# 1_J_LINK_PCB.net
KiCad netlist of a schematic drawn in EasyEDA Pro
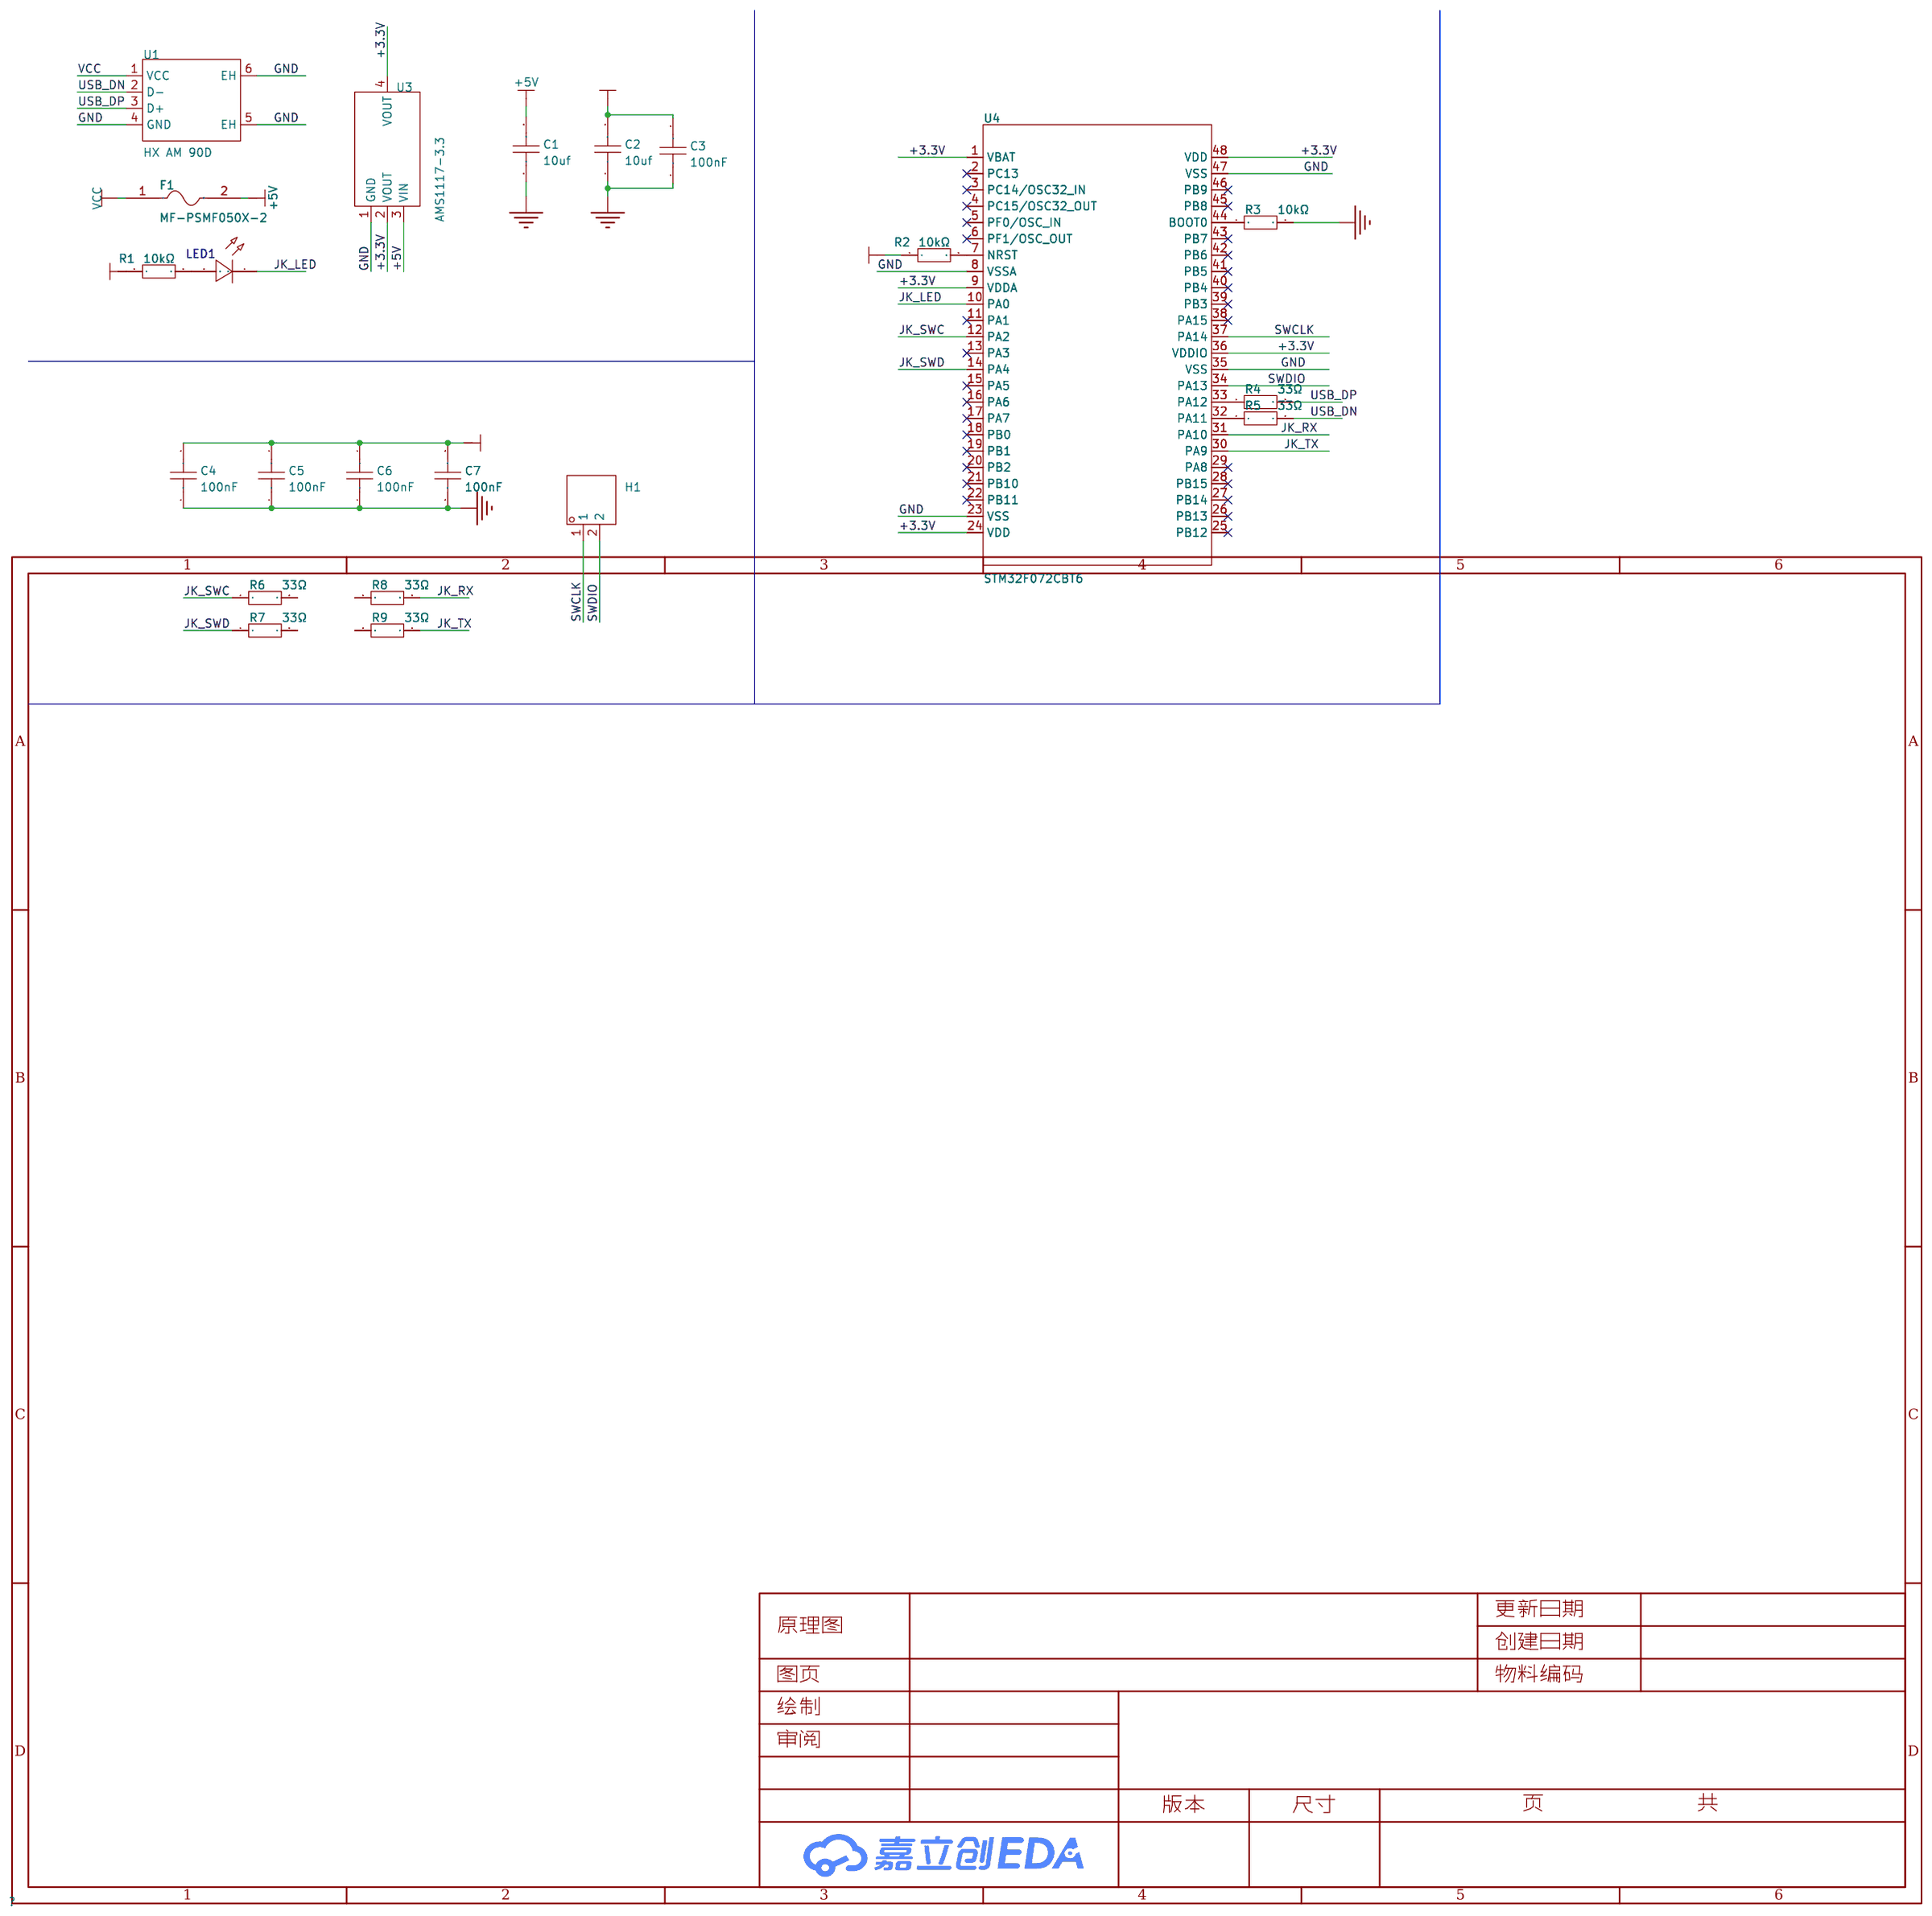
[diagram p0: schematic sheet]

(export (version "E")
  (design (tool "Eeschema 10.0.6"))
  (components
    (comp (ref "C1")
      (value "10uf")
      (footprint "easyedapro:C0603")
      (libsource (lib "easyedapro") (part "CapAcitance"))
    )
    (comp (ref "C2")
      (value "10uf")
      (footprint "easyedapro:C0603")
      (libsource (lib "easyedapro") (part "CapAcitance"))
    )
    (comp (ref "C3")
      (value "100nF")
      (footprint "easyedapro:C0603")
      (libsource (lib "easyedapro") (part "CapAcitance"))
    )
    (comp (ref "C4")
      (value "100nF")
      (footprint "easyedapro:C0603")
      (description "容值:100nF;精度:±10%;额定电压:50V;温度系数:X7R;")
      (fields
        (field (name "Manufacturer Part") "CGA0603X7R104K500JT")
        (field (name "Manufacturer") "HRE(芯声)")
      )
      (libsource (lib "easyedapro") (part "CGA0603X7R104K500JT"))
    )
    (comp (ref "C5")
      (value "100nF")
      (footprint "easyedapro:C0603")
      (description "容值:100nF;精度:±10%;额定电压:50V;温度系数:X7R;")
      (fields
        (field (name "Manufacturer Part") "CGA0603X7R104K500JT")
        (field (name "Manufacturer") "HRE(芯声)")
      )
      (libsource (lib "easyedapro") (part "CGA0603X7R104K500JT"))
    )
    (comp (ref "C6")
      (value "100nF")
      (footprint "easyedapro:C0603")
      (description "容值:100nF;精度:±10%;额定电压:50V;温度系数:X7R;")
      (fields
        (field (name "Manufacturer Part") "CGA0603X7R104K500JT")
        (field (name "Manufacturer") "HRE(芯声)")
      )
      (libsource (lib "easyedapro") (part "CGA0603X7R104K500JT"))
    )
    (comp (ref "C7")
      (value "100nF")
      (footprint "easyedapro:C0603")
      (description "容值:100nF;精度:±10%;额定电压:50V;温度系数:X7R;")
      (fields
        (field (name "Manufacturer Part") "CGA0603X7R104K500JT")
        (field (name "Manufacturer") "HRE(芯声)")
      )
      (libsource (lib "easyedapro") (part "CGA0603X7R104K500JT"))
    )
    (comp (ref "F1")
      (value "MF-PSMF050X-2")
      (footprint "easyedapro:F0805")
      (description "最大电压:6V;最大电流:40A;保持电流:500mA;跳闸电流:1A;")
      (fields (field (name "Manufacturer") "BOURNS"))
      (libsource (lib "easyedapro") (part "MF-PSMF050X-2"))
    )
    (comp (ref "H1")
      (value "~")
      (footprint "easyedapro:HDR-TH_2P-P2.54-V-M-1")
      (libsource (lib "easyedapro") (part "210S-1*2P L=11.6MMGold-plated black"))
    )
    (comp (ref "LED1")
      (value "~")
      (footprint "easyedapro:LED_0603")
      (libsource (lib "easyedapro") (part "LED_B"))
    )
    (comp (ref "R1")
      (value "10kΩ")
      (footprint "easyedapro:R0603")
      (description "电阻类型:厚膜电阻;阻值:10kΩ;精度:±1%;功率:100mW;最大工作电压:75V;温度系数:±100ppm/°C;")
      (fields
        (field (name "Manufacturer Part") "0603WAF1002T5E")
        (field (name "Manufacturer") "UNI-ROYAL(厚声)")
      )
      (libsource (lib "easyedapro") (part "0603WAF1002T5E"))
    )
    (comp (ref "R2")
      (value "10kΩ")
      (footprint "easyedapro:R0603")
      (description "电阻类型:厚膜电阻;阻值:10kΩ;精度:±1%;功率:100mW;最大工作电压:75V;温度系数:±100ppm/°C;")
      (fields
        (field (name "Manufacturer Part") "0603WAF1002T5E")
        (field (name "Manufacturer") "UNI-ROYAL(厚声)")
      )
      (libsource (lib "easyedapro") (part "0603WAF1002T5E"))
    )
    (comp (ref "R3")
      (value "10kΩ")
      (footprint "easyedapro:R0603")
      (description "电阻类型:厚膜电阻;阻值:10kΩ;精度:±1%;功率:100mW;最大工作电压:75V;温度系数:±100ppm/°C;")
      (fields
        (field (name "Manufacturer Part") "0603WAF1002T5E")
        (field (name "Manufacturer") "UNI-ROYAL(厚声)")
      )
      (libsource (lib "easyedapro") (part "0603WAF1002T5E"))
    )
    (comp (ref "R4")
      (value "33Ω")
      (footprint "easyedapro:R0603")
      (description "电阻类型:厚膜电阻;阻值:10kΩ;精度:±1%;功率:100mW;最大工作电压:75V;温度系数:±100ppm/°C;")
      (fields
        (field (name "Manufacturer Part") "0603WAF1002T5E")
        (field (name "Manufacturer") "UNI-ROYAL(厚声)")
      )
      (libsource (lib "easyedapro") (part "0603WAF1002T5E"))
    )
    (comp (ref "R5")
      (value "33Ω")
      (footprint "easyedapro:R0603")
      (description "电阻类型:厚膜电阻;阻值:10kΩ;精度:±1%;功率:100mW;最大工作电压:75V;温度系数:±100ppm/°C;")
      (fields
        (field (name "Manufacturer Part") "0603WAF1002T5E")
        (field (name "Manufacturer") "UNI-ROYAL(厚声)")
      )
      (libsource (lib "easyedapro") (part "0603WAF1002T5E"))
    )
    (comp (ref "R6")
      (value "33Ω")
      (footprint "easyedapro:R0603")
      (description "电阻类型:厚膜电阻;阻值:10kΩ;精度:±1%;功率:100mW;最大工作电压:75V;温度系数:±100ppm/°C;")
      (fields
        (field (name "Manufacturer Part") "0603WAF1002T5E")
        (field (name "Manufacturer") "UNI-ROYAL(厚声)")
      )
      (libsource (lib "easyedapro") (part "0603WAF1002T5E"))
    )
    (comp (ref "R7")
      (value "33Ω")
      (footprint "easyedapro:R0603")
      (description "电阻类型:厚膜电阻;阻值:10kΩ;精度:±1%;功率:100mW;最大工作电压:75V;温度系数:±100ppm/°C;")
      (fields
        (field (name "Manufacturer Part") "0603WAF1002T5E")
        (field (name "Manufacturer") "UNI-ROYAL(厚声)")
      )
      (libsource (lib "easyedapro") (part "0603WAF1002T5E"))
    )
    (comp (ref "R8")
      (value "33Ω")
      (footprint "easyedapro:R0603")
      (description "电阻类型:厚膜电阻;阻值:10kΩ;精度:±1%;功率:100mW;最大工作电压:75V;温度系数:±100ppm/°C;")
      (fields
        (field (name "Manufacturer Part") "0603WAF1002T5E")
        (field (name "Manufacturer") "UNI-ROYAL(厚声)")
      )
      (libsource (lib "easyedapro") (part "0603WAF1002T5E"))
    )
    (comp (ref "R9")
      (value "33Ω")
      (footprint "easyedapro:R0603")
      (description "电阻类型:厚膜电阻;阻值:10kΩ;精度:±1%;功率:100mW;最大工作电压:75V;温度系数:±100ppm/°C;")
      (fields
        (field (name "Manufacturer Part") "0603WAF1002T5E")
        (field (name "Manufacturer") "UNI-ROYAL(厚声)")
      )
      (libsource (lib "easyedapro") (part "0603WAF1002T5E"))
    )
    (comp (ref "U1")
      (value "HX AM 90D")
      (footprint "easyedapro:USB-A-TH_HANXIA_HXAM90D")
      (description "连接器类型:Type-A;标准:USB 2.0;公母:公;端口数量:1;触点数量:4P;额定电流 - 电源:1.5A;工作温度范围:-25°C~+85°C;")
      (fields (field (name "Manufacturer") "hanxia(韩下)"))
      (libsource (lib "easyedapro") (part "HX AM 90D"))
    )
    (comp (ref "U3")
      (value "AMS1117-3.3")
      (footprint "easyedapro:SOT-223-3_L6.5-W3.4-P2.30-LS7.0-BR")
      (description "输出类型:固定;工作电压:-;输出电压:3.3V;输出电流:1A;电源纹波抑制比(PSRR):72dB@(120Hz);输出极性:正极;")
      (fields (field (name "Manufacturer") "AMS"))
      (libsource (lib "easyedapro") (part "AMS1117-3.3"))
    )
    (comp (ref "U4")
      (value "STM32F072CBT6")
      (footprint "easyedapro:LQFP-48_L7.0-W7.0-P0.50-LS9.0-BL")
      (description "CPU内核:ARM-M0;CPU最大主频:48MHz;应用领域:-;")
      (fields (field (name "Manufacturer") "ST(意法半导体)"))
      (libsource (lib "easyedapro") (part "STM32F072CBT6"))
    )
  )
  (nets
    (net (code "1") (name "+3.3V") (class "Default")
      (node (ref "C2") (pin "2") (pinfunction "2_2") (pintype "input"))
      (node (ref "C3") (pin "2") (pinfunction "2_2") (pintype "input"))
      (node (ref "C4") (pin "2") (pinfunction "2_2") (pintype "unspecified"))
      (node (ref "C5") (pin "2") (pinfunction "2_2") (pintype "unspecified"))
      (node (ref "C6") (pin "2") (pinfunction "2_2") (pintype "unspecified"))
      (node (ref "C7") (pin "2") (pinfunction "2_2") (pintype "unspecified"))
      (node (ref "R1") (pin "1") (pinfunction "1_1") (pintype "input"))
      (node (ref "R2") (pin "1") (pinfunction "1_1") (pintype "input"))
      (node (ref "U3") (pin "2") (pinfunction "VOUT_2") (pintype "unspecified"))
      (node (ref "U3") (pin "4") (pinfunction "VOUT_4") (pintype "unspecified"))
      (node (ref "U4") (pin "1") (pinfunction "VBAT_1") (pintype "unspecified"))
      (node (ref "U4") (pin "24") (pinfunction "VDD_24") (pintype "unspecified"))
      (node (ref "U4") (pin "36") (pinfunction "VDDIO_36") (pintype "unspecified"))
      (node (ref "U4") (pin "48") (pinfunction "VDD_48") (pintype "unspecified"))
      (node (ref "U4") (pin "9") (pinfunction "VDDA_9") (pintype "unspecified"))
    )
    (net (code "2") (name "+5V") (class "Default")
      (node (ref "C1") (pin "2") (pinfunction "2_2") (pintype "input"))
      (node (ref "F1") (pin "2") (pinfunction "2_2") (pintype "unspecified"))
      (node (ref "U3") (pin "3") (pinfunction "VIN_3") (pintype "unspecified"))
    )
    (net (code "3") (name "/JK_LED") (class "Default")
      (node (ref "LED1") (pin "1") (pinfunction "C_1") (pintype "input"))
      (node (ref "U4") (pin "10") (pinfunction "PA0_10") (pintype "unspecified"))
    )
    (net (code "4") (name "/JK_RX") (class "Default")
      (node (ref "R8") (pin "2") (pinfunction "2_2") (pintype "input"))
      (node (ref "U4") (pin "31") (pinfunction "PA10_31") (pintype "unspecified"))
    )
    (net (code "5") (name "/JK_SWC") (class "Default")
      (node (ref "R6") (pin "1") (pinfunction "1_1") (pintype "input"))
      (node (ref "U4") (pin "12") (pinfunction "PA2_12") (pintype "unspecified"))
    )
    (net (code "6") (name "/JK_SWD") (class "Default")
      (node (ref "R7") (pin "1") (pinfunction "1_1") (pintype "input"))
      (node (ref "U4") (pin "14") (pinfunction "PA4_14") (pintype "unspecified"))
    )
    (net (code "7") (name "/JK_TX") (class "Default")
      (node (ref "R9") (pin "2") (pinfunction "2_2") (pintype "input"))
      (node (ref "U4") (pin "30") (pinfunction "PA9_30") (pintype "unspecified"))
    )
    (net (code "8") (name "/SWCLK") (class "Default")
      (node (ref "H1") (pin "1") (pinfunction "1_1") (pintype "unspecified"))
      (node (ref "U4") (pin "37") (pinfunction "PA14_37") (pintype "unspecified"))
    )
    (net (code "9") (name "/SWDIO") (class "Default")
      (node (ref "H1") (pin "2") (pinfunction "2_2") (pintype "unspecified"))
      (node (ref "U4") (pin "34") (pinfunction "PA13_34") (pintype "unspecified"))
    )
    (net (code "10") (name "/USB_DN") (class "Default")
      (node (ref "R5") (pin "2") (pinfunction "2_2") (pintype "input"))
      (node (ref "U1") (pin "2") (pinfunction "D-_2") (pintype "input"))
    )
    (net (code "11") (name "/USB_DP") (class "Default")
      (node (ref "R4") (pin "2") (pinfunction "2_2") (pintype "input"))
      (node (ref "U1") (pin "3") (pinfunction "D+_3") (pintype "input"))
    )
    (net (code "12") (name "GND") (class "Default")
      (node (ref "C1") (pin "1") (pinfunction "1_1") (pintype "input"))
      (node (ref "C2") (pin "1") (pinfunction "1_1") (pintype "input"))
      (node (ref "C3") (pin "1") (pinfunction "1_1") (pintype "input"))
      (node (ref "C4") (pin "1") (pinfunction "1_1") (pintype "unspecified"))
      (node (ref "C5") (pin "1") (pinfunction "1_1") (pintype "unspecified"))
      (node (ref "C6") (pin "1") (pinfunction "1_1") (pintype "unspecified"))
      (node (ref "C7") (pin "1") (pinfunction "1_1") (pintype "unspecified"))
      (node (ref "R3") (pin "2") (pinfunction "2_2") (pintype "input"))
      (node (ref "U1") (pin "4") (pinfunction "GND_4") (pintype "input"))
      (node (ref "U1") (pin "5") (pinfunction "EH_5") (pintype "unspecified"))
      (node (ref "U1") (pin "6") (pinfunction "EH_6") (pintype "unspecified"))
      (node (ref "U3") (pin "1") (pinfunction "GND_1") (pintype "unspecified"))
      (node (ref "U4") (pin "23") (pinfunction "VSS_23") (pintype "unspecified"))
      (node (ref "U4") (pin "35") (pinfunction "VSS_35") (pintype "unspecified"))
      (node (ref "U4") (pin "47") (pinfunction "VSS_47") (pintype "unspecified"))
      (node (ref "U4") (pin "8") (pinfunction "VSSA_8") (pintype "unspecified"))
    )
    (net (code "13") (name "Net-(LED1-A)") (class "Default")
      (node (ref "LED1") (pin "2") (pinfunction "A_2") (pintype "input"))
      (node (ref "R1") (pin "2") (pinfunction "2_2") (pintype "input"))
    )
    (net (code "14") (name "Net-(U4-BOOT0)") (class "Default")
      (node (ref "R3") (pin "1") (pinfunction "1_1") (pintype "input"))
      (node (ref "U4") (pin "44") (pinfunction "BOOT0_44") (pintype "unspecified"))
    )
    (net (code "15") (name "Net-(U4-NRST)") (class "Default")
      (node (ref "R2") (pin "2") (pinfunction "2_2") (pintype "input"))
      (node (ref "U4") (pin "7") (pinfunction "NRST_7") (pintype "unspecified"))
    )
    (net (code "16") (name "Net-(U4-PA11)") (class "Default")
      (node (ref "R5") (pin "1") (pinfunction "1_1") (pintype "input"))
      (node (ref "U4") (pin "32") (pinfunction "PA11_32") (pintype "unspecified"))
    )
    (net (code "17") (name "Net-(U4-PA12)") (class "Default")
      (node (ref "R4") (pin "1") (pinfunction "1_1") (pintype "input"))
      (node (ref "U4") (pin "33") (pinfunction "PA12_33") (pintype "unspecified"))
    )
    (net (code "18") (name "VCC") (class "Default")
      (node (ref "F1") (pin "1") (pinfunction "1_1") (pintype "unspecified"))
      (node (ref "U1") (pin "1") (pinfunction "VCC_1") (pintype "input"))
    )
    (net (code "19") (name "unconnected-(R6-Pad2)") (class "Default")
      (node (ref "R6") (pin "2") (pinfunction "2_2") (pintype "input"))
    )
    (net (code "20") (name "unconnected-(R7-Pad2)") (class "Default")
      (node (ref "R7") (pin "2") (pinfunction "2_2") (pintype "input"))
    )
    (net (code "21") (name "unconnected-(R8-Pad1)") (class "Default")
      (node (ref "R8") (pin "1") (pinfunction "1_1") (pintype "input"))
    )
    (net (code "22") (name "unconnected-(R9-Pad1)") (class "Default")
      (node (ref "R9") (pin "1") (pinfunction "1_1") (pintype "input"))
    )
    (net (code "23") (name "unconnected-(U4-PA1-Pad11)") (class "Default")
      (node (ref "U4") (pin "11") (pinfunction "PA1_11") (pintype "unspecified+no_connect"))
    )
    (net (code "24") (name "unconnected-(U4-PA3-Pad13)") (class "Default")
      (node (ref "U4") (pin "13") (pinfunction "PA3_13") (pintype "unspecified+no_connect"))
    )
    (net (code "25") (name "unconnected-(U4-PA5-Pad15)") (class "Default")
      (node (ref "U4") (pin "15") (pinfunction "PA5_15") (pintype "unspecified+no_connect"))
    )
    (net (code "26") (name "unconnected-(U4-PA6-Pad16)") (class "Default")
      (node (ref "U4") (pin "16") (pinfunction "PA6_16") (pintype "unspecified+no_connect"))
    )
    (net (code "27") (name "unconnected-(U4-PA7-Pad17)") (class "Default")
      (node (ref "U4") (pin "17") (pinfunction "PA7_17") (pintype "unspecified+no_connect"))
    )
    (net (code "28") (name "unconnected-(U4-PA8-Pad29)") (class "Default")
      (node (ref "U4") (pin "29") (pinfunction "PA8_29") (pintype "unspecified+no_connect"))
    )
    (net (code "29") (name "unconnected-(U4-PA15-Pad38)") (class "Default")
      (node (ref "U4") (pin "38") (pinfunction "PA15_38") (pintype "unspecified+no_connect"))
    )
    (net (code "30") (name "unconnected-(U4-PB0-Pad18)") (class "Default")
      (node (ref "U4") (pin "18") (pinfunction "PB0_18") (pintype "unspecified+no_connect"))
    )
    (net (code "31") (name "unconnected-(U4-PB1-Pad19)") (class "Default")
      (node (ref "U4") (pin "19") (pinfunction "PB1_19") (pintype "unspecified+no_connect"))
    )
    (net (code "32") (name "unconnected-(U4-PB2-Pad20)") (class "Default")
      (node (ref "U4") (pin "20") (pinfunction "PB2_20") (pintype "unspecified+no_connect"))
    )
    (net (code "33") (name "unconnected-(U4-PB3-Pad39)") (class "Default")
      (node (ref "U4") (pin "39") (pinfunction "PB3_39") (pintype "unspecified+no_connect"))
    )
    (net (code "34") (name "unconnected-(U4-PB4-Pad40)") (class "Default")
      (node (ref "U4") (pin "40") (pinfunction "PB4_40") (pintype "unspecified+no_connect"))
    )
    (net (code "35") (name "unconnected-(U4-PB5-Pad41)") (class "Default")
      (node (ref "U4") (pin "41") (pinfunction "PB5_41") (pintype "unspecified+no_connect"))
    )
    (net (code "36") (name "unconnected-(U4-PB6-Pad42)") (class "Default")
      (node (ref "U4") (pin "42") (pinfunction "PB6_42") (pintype "unspecified+no_connect"))
    )
    (net (code "37") (name "unconnected-(U4-PB7-Pad43)") (class "Default")
      (node (ref "U4") (pin "43") (pinfunction "PB7_43") (pintype "unspecified+no_connect"))
    )
    (net (code "38") (name "unconnected-(U4-PB8-Pad45)") (class "Default")
      (node (ref "U4") (pin "45") (pinfunction "PB8_45") (pintype "unspecified+no_connect"))
    )
    (net (code "39") (name "unconnected-(U4-PB9-Pad46)") (class "Default")
      (node (ref "U4") (pin "46") (pinfunction "PB9_46") (pintype "unspecified+no_connect"))
    )
    (net (code "40") (name "unconnected-(U4-PB10-Pad21)") (class "Default")
      (node (ref "U4") (pin "21") (pinfunction "PB10_21") (pintype "unspecified+no_connect"))
    )
    (net (code "41") (name "unconnected-(U4-PB11-Pad22)") (class "Default")
      (node (ref "U4") (pin "22") (pinfunction "PB11_22") (pintype "unspecified+no_connect"))
    )
    (net (code "42") (name "unconnected-(U4-PB12-Pad25)") (class "Default")
      (node (ref "U4") (pin "25") (pinfunction "PB12_25") (pintype "unspecified+no_connect"))
    )
    (net (code "43") (name "unconnected-(U4-PB13-Pad26)") (class "Default")
      (node (ref "U4") (pin "26") (pinfunction "PB13_26") (pintype "unspecified+no_connect"))
    )
    (net (code "44") (name "unconnected-(U4-PB14-Pad27)") (class "Default")
      (node (ref "U4") (pin "27") (pinfunction "PB14_27") (pintype "unspecified+no_connect"))
    )
    (net (code "45") (name "unconnected-(U4-PB15-Pad28)") (class "Default")
      (node (ref "U4") (pin "28") (pinfunction "PB15_28") (pintype "unspecified+no_connect"))
    )
    (net (code "46") (name "unconnected-(U4-PC13-Pad2)") (class "Default")
      (node (ref "U4") (pin "2") (pinfunction "PC13_2") (pintype "unspecified+no_connect"))
    )
    (net (code "47") (name "unconnected-(U4-PC14{slash}OSC32_IN-Pad3)") (class "Default")
      (node (ref "U4") (pin "3") (pinfunction "PC14/OSC32_IN_3") (pintype "unspecified+no_connect"))
    )
    (net (code "48") (name "unconnected-(U4-PC15{slash}OSC32_OUT-Pad4)") (class "Default")
      (node (ref "U4") (pin "4") (pinfunction "PC15/OSC32_OUT_4") (pintype "unspecified+no_connect"))
    )
    (net (code "49") (name "unconnected-(U4-PF0{slash}OSC_IN-Pad5)") (class "Default")
      (node (ref "U4") (pin "5") (pinfunction "PF0/OSC_IN_5") (pintype "unspecified+no_connect"))
    )
    (net (code "50") (name "unconnected-(U4-PF1{slash}OSC_OUT-Pad6)") (class "Default")
      (node (ref "U4") (pin "6") (pinfunction "PF1/OSC_OUT_6") (pintype "unspecified+no_connect"))
    )
  )
)
